# 7-Segment_SCH.net
KiCad netlist of a schematic drawn in Altium Designer
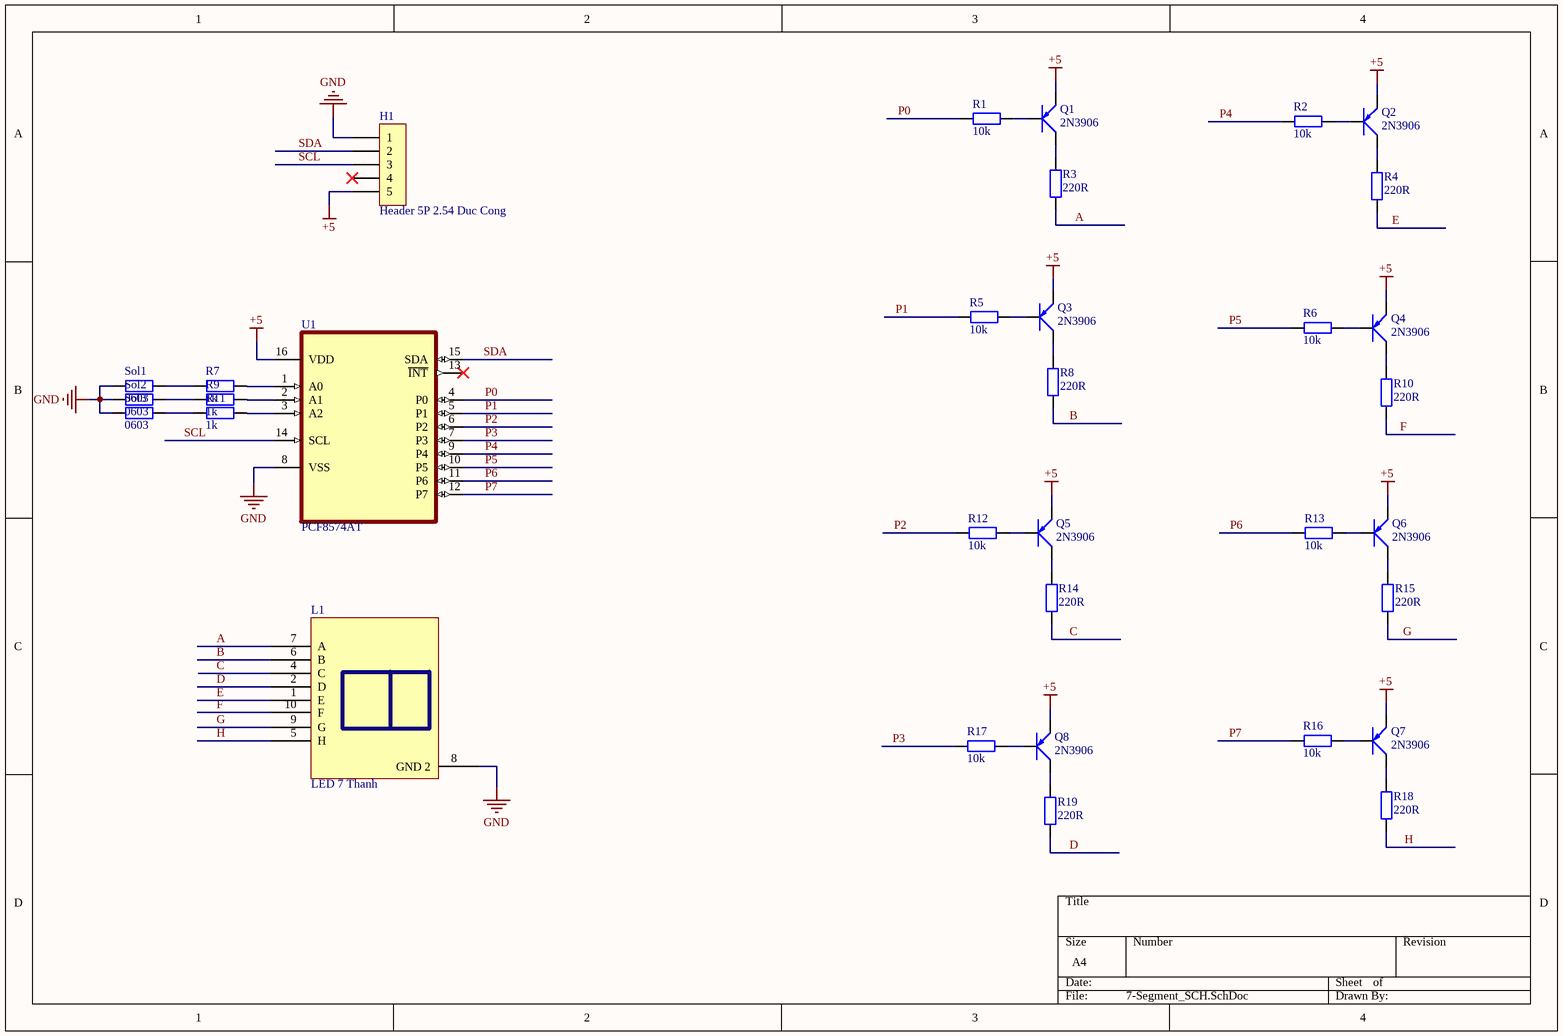
[diagram p0: 7-Segment_SCH.SchDoc]

(export (version "E")
  (design (tool "Eeschema 10.0.6"))
  (components
    (comp (ref "H1")
      (value "Header 5P 2.54 Duc Cong")
      (footprint "Header 5P DC 2.54")
      (description "Cắm")
      (libsource (lib "namnt_Lib") (part "Header 5P 2.54 Duc Cong"))
    )
    (comp (ref "L1")
      (value "LED 7 Thanh")
      (footprint "LED 7x1 0.28")
      (description "Dán")
      (libsource (lib "namnt_Lib") (part "LED 7x1 0.28 Katot"))
    )
    (comp (ref "Q1")
      (value "2N3906")
      (footprint "SOT23")
      (description "PNP 600mW, ECB")
      (libsource (lib "namnt_Lib") (part "Trans A1015 BA SMD"))
    )
    (comp (ref "Q2")
      (value "2N3906")
      (footprint "SOT23")
      (description "PNP 600mW, ECB")
      (libsource (lib "namnt_Lib") (part "Trans A1015 BA SMD"))
    )
    (comp (ref "Q3")
      (value "2N3906")
      (footprint "SOT23")
      (description "PNP 600mW, ECB")
      (libsource (lib "namnt_Lib") (part "Trans A1015 BA SMD"))
    )
    (comp (ref "Q4")
      (value "2N3906")
      (footprint "SOT23")
      (description "PNP 600mW, ECB")
      (libsource (lib "namnt_Lib") (part "Trans A1015 BA SMD"))
    )
    (comp (ref "Q5")
      (value "2N3906")
      (footprint "SOT23")
      (description "PNP 600mW, ECB")
      (libsource (lib "namnt_Lib") (part "Trans A1015 BA SMD"))
    )
    (comp (ref "Q6")
      (value "2N3906")
      (footprint "SOT23")
      (description "PNP 600mW, ECB")
      (libsource (lib "namnt_Lib") (part "Trans A1015 BA SMD"))
    )
    (comp (ref "Q7")
      (value "2N3906")
      (footprint "SOT23")
      (description "PNP 600mW, ECB")
      (libsource (lib "namnt_Lib") (part "Trans A1015 BA SMD"))
    )
    (comp (ref "Q8")
      (value "2N3906")
      (footprint "SOT23")
      (description "PNP 600mW, ECB")
      (libsource (lib "namnt_Lib") (part "Trans A1015 BA SMD"))
    )
    (comp (ref "R1")
      (value "10k")
      (footprint "tro smd 0603")
      (description "Dán")
      (libsource (lib "namnt_Lib") (part "Tro 0603 1% 10k"))
    )
    (comp (ref "R2")
      (value "10k")
      (footprint "tro smd 0603")
      (description "Dán")
      (libsource (lib "namnt_Lib") (part "Tro 0603 1% 10k"))
    )
    (comp (ref "R3")
      (value "220R")
      (footprint "tro smd 0603")
      (description "Dán")
      (libsource (lib "namnt_Lib") (part "Tro 0603 5% 220R"))
    )
    (comp (ref "R4")
      (value "220R")
      (footprint "tro smd 0603")
      (description "Dán")
      (libsource (lib "namnt_Lib") (part "Tro 0603 5% 220R"))
    )
    (comp (ref "R5")
      (value "10k")
      (footprint "tro smd 0603")
      (description "Dán")
      (libsource (lib "namnt_Lib") (part "Tro 0603 1% 10k"))
    )
    (comp (ref "R6")
      (value "10k")
      (footprint "tro smd 0603")
      (description "Dán")
      (libsource (lib "namnt_Lib") (part "Tro 0603 1% 10k"))
    )
    (comp (ref "R7")
      (value "1k")
      (footprint "tro smd 0603")
      (description "Dán")
      (libsource (lib "namnt_Lib") (part "Tro 0603 1% 1k"))
    )
    (comp (ref "R8")
      (value "220R")
      (footprint "tro smd 0603")
      (description "Dán")
      (libsource (lib "namnt_Lib") (part "Tro 0603 5% 220R"))
    )
    (comp (ref "R9")
      (value "1k")
      (footprint "tro smd 0603")
      (description "Dán")
      (libsource (lib "namnt_Lib") (part "Tro 0603 1% 1k"))
    )
    (comp (ref "R10")
      (value "220R")
      (footprint "tro smd 0603")
      (description "Dán")
      (libsource (lib "namnt_Lib") (part "Tro 0603 5% 220R"))
    )
    (comp (ref "R11")
      (value "1k")
      (footprint "tro smd 0603")
      (description "Dán")
      (libsource (lib "namnt_Lib") (part "Tro 0603 1% 1k"))
    )
    (comp (ref "R12")
      (value "10k")
      (footprint "tro smd 0603")
      (description "Dán")
      (libsource (lib "namnt_Lib") (part "Tro 0603 1% 10k"))
    )
    (comp (ref "R13")
      (value "10k")
      (footprint "tro smd 0603")
      (description "Dán")
      (libsource (lib "namnt_Lib") (part "Tro 0603 1% 10k"))
    )
    (comp (ref "R14")
      (value "220R")
      (footprint "tro smd 0603")
      (description "Dán")
      (libsource (lib "namnt_Lib") (part "Tro 0603 5% 220R"))
    )
    (comp (ref "R15")
      (value "220R")
      (footprint "tro smd 0603")
      (description "Dán")
      (libsource (lib "namnt_Lib") (part "Tro 0603 5% 220R"))
    )
    (comp (ref "R16")
      (value "10k")
      (footprint "tro smd 0603")
      (description "Dán")
      (libsource (lib "namnt_Lib") (part "Tro 0603 1% 10k"))
    )
    (comp (ref "R17")
      (value "10k")
      (footprint "tro smd 0603")
      (description "Dán")
      (libsource (lib "namnt_Lib") (part "Tro 0603 1% 10k"))
    )
    (comp (ref "R18")
      (value "220R")
      (footprint "tro smd 0603")
      (description "Dán")
      (libsource (lib "namnt_Lib") (part "Tro 0603 5% 220R"))
    )
    (comp (ref "R19")
      (value "220R")
      (footprint "tro smd 0603")
      (description "Dán")
      (libsource (lib "namnt_Lib") (part "Tro 0603 5% 220R"))
    )
    (comp (ref "Sol1")
      (value "0603")
      (footprint "Solder 0603")
      (description "Dán")
      (libsource (lib "namnt_Lib") (part "Solder 0603"))
    )
    (comp (ref "Sol2")
      (value "0603")
      (footprint "Solder 0603")
      (description "Dán")
      (libsource (lib "namnt_Lib") (part "Solder 0603"))
    )
    (comp (ref "Sol3")
      (value "0603")
      (footprint "Solder 0603")
      (description "Dán")
      (libsource (lib "namnt_Lib") (part "Solder 0603"))
    )
    (comp (ref "U1")
      (value "PCF8574AT")
      (footprint "SOIC127P1032X265-16N")
      (description "IÂ²C Bus IC Operating temperature: -40...+85 Â°C Power supply: 2.5...6 V Package: SO-16W")
      (fields (field (name "MF") "NXP USA"))
      (libsource (lib "namnt_Lib") (part "PCF8574AT"))
    )
  )
  (nets
    (net (code "1") (name "+5") (class "Default")
      (node (ref "H1") (pin "5") (pinfunction "5_5") (pintype "passive"))
      (node (ref "Q1") (pin "2") (pinfunction "E_2") (pintype "passive"))
      (node (ref "Q2") (pin "2") (pinfunction "E_2") (pintype "passive"))
      (node (ref "Q3") (pin "2") (pinfunction "E_2") (pintype "passive"))
      (node (ref "Q4") (pin "2") (pinfunction "E_2") (pintype "passive"))
      (node (ref "Q5") (pin "2") (pinfunction "E_2") (pintype "passive"))
      (node (ref "Q6") (pin "2") (pinfunction "E_2") (pintype "passive"))
      (node (ref "Q7") (pin "2") (pinfunction "E_2") (pintype "passive"))
      (node (ref "Q8") (pin "2") (pinfunction "E_2") (pintype "passive"))
      (node (ref "U1") (pin "16") (pinfunction "VDD_16") (pintype "power_in"))
    )
    (net (code "2") (name "/A") (class "Default")
      (node (ref "L1") (pin "7") (pinfunction "A_7") (pintype "passive"))
      (node (ref "R3") (pin "1") (pinfunction "1_1") (pintype "passive"))
    )
    (net (code "3") (name "/B") (class "Default")
      (node (ref "L1") (pin "6") (pinfunction "B_6") (pintype "passive"))
      (node (ref "R8") (pin "1") (pinfunction "1_1") (pintype "passive"))
    )
    (net (code "4") (name "/C") (class "Default")
      (node (ref "L1") (pin "4") (pinfunction "C_4") (pintype "passive"))
      (node (ref "R14") (pin "1") (pinfunction "1_1") (pintype "passive"))
    )
    (net (code "5") (name "/D") (class "Default")
      (node (ref "L1") (pin "2") (pinfunction "D_2") (pintype "passive"))
      (node (ref "R19") (pin "1") (pinfunction "1_1") (pintype "passive"))
    )
    (net (code "6") (name "/E") (class "Default")
      (node (ref "L1") (pin "1") (pinfunction "E_1") (pintype "passive"))
      (node (ref "R4") (pin "1") (pinfunction "1_1") (pintype "passive"))
    )
    (net (code "7") (name "/F") (class "Default")
      (node (ref "L1") (pin "10") (pinfunction "F_10") (pintype "passive"))
      (node (ref "R10") (pin "1") (pinfunction "1_1") (pintype "passive"))
    )
    (net (code "8") (name "/G") (class "Default")
      (node (ref "L1") (pin "9") (pinfunction "G_9") (pintype "passive"))
      (node (ref "R15") (pin "1") (pinfunction "1_1") (pintype "passive"))
    )
    (net (code "9") (name "/H") (class "Default")
      (node (ref "L1") (pin "5") (pinfunction "H_5") (pintype "passive"))
      (node (ref "R18") (pin "1") (pinfunction "1_1") (pintype "passive"))
    )
    (net (code "10") (name "/P0") (class "Default")
      (node (ref "R1") (pin "1") (pinfunction "1_1") (pintype "passive"))
      (node (ref "U1") (pin "4") (pinfunction "P0_4") (pintype "bidirectional"))
    )
    (net (code "11") (name "/P1") (class "Default")
      (node (ref "R5") (pin "1") (pinfunction "1_1") (pintype "passive"))
      (node (ref "U1") (pin "5") (pinfunction "P1_5") (pintype "bidirectional"))
    )
    (net (code "12") (name "/P2") (class "Default")
      (node (ref "R12") (pin "1") (pinfunction "1_1") (pintype "passive"))
      (node (ref "U1") (pin "6") (pinfunction "P2_6") (pintype "bidirectional"))
    )
    (net (code "13") (name "/P3") (class "Default")
      (node (ref "R17") (pin "1") (pinfunction "1_1") (pintype "passive"))
      (node (ref "U1") (pin "7") (pinfunction "P3_7") (pintype "bidirectional"))
    )
    (net (code "14") (name "/P4") (class "Default")
      (node (ref "R2") (pin "1") (pinfunction "1_1") (pintype "passive"))
      (node (ref "U1") (pin "9") (pinfunction "P4_9") (pintype "bidirectional"))
    )
    (net (code "15") (name "/P5") (class "Default")
      (node (ref "R6") (pin "1") (pinfunction "1_1") (pintype "passive"))
      (node (ref "U1") (pin "10") (pinfunction "P5_10") (pintype "bidirectional"))
    )
    (net (code "16") (name "/P6") (class "Default")
      (node (ref "R13") (pin "1") (pinfunction "1_1") (pintype "passive"))
      (node (ref "U1") (pin "11") (pinfunction "P6_11") (pintype "bidirectional"))
    )
    (net (code "17") (name "/P7") (class "Default")
      (node (ref "R16") (pin "1") (pinfunction "1_1") (pintype "passive"))
      (node (ref "U1") (pin "12") (pinfunction "P7_12") (pintype "bidirectional"))
    )
    (net (code "18") (name "/SCL") (class "Default")
      (node (ref "H1") (pin "3") (pinfunction "3_3") (pintype "passive"))
      (node (ref "U1") (pin "14") (pinfunction "SCL_14") (pintype "input"))
    )
    (net (code "19") (name "/SDA") (class "Default")
      (node (ref "H1") (pin "2") (pinfunction "2_2") (pintype "passive"))
      (node (ref "U1") (pin "15") (pinfunction "SDA_15") (pintype "bidirectional"))
    )
    (net (code "20") (name "GND") (class "Default")
      (node (ref "H1") (pin "1") (pinfunction "1_1") (pintype "passive"))
      (node (ref "L1") (pin "8") (pinfunction "GND_2_8") (pintype "passive"))
      (node (ref "Sol1") (pin "1") (pinfunction "1_1") (pintype "passive"))
      (node (ref "Sol2") (pin "1") (pinfunction "1_1") (pintype "passive"))
      (node (ref "Sol3") (pin "1") (pinfunction "1_1") (pintype "passive"))
      (node (ref "U1") (pin "8") (pinfunction "VSS_8") (pintype "passive"))
    )
    (net (code "21") (name "Net-(Q1-B)") (class "Default")
      (node (ref "Q1") (pin "1") (pinfunction "B_1") (pintype "passive"))
      (node (ref "R1") (pin "2") (pinfunction "2_2") (pintype "passive"))
    )
    (net (code "22") (name "Net-(Q1-C)") (class "Default")
      (node (ref "Q1") (pin "3") (pinfunction "C_3") (pintype "passive"))
      (node (ref "R3") (pin "2") (pinfunction "2_2") (pintype "passive"))
    )
    (net (code "23") (name "Net-(Q2-B)") (class "Default")
      (node (ref "Q2") (pin "1") (pinfunction "B_1") (pintype "passive"))
      (node (ref "R2") (pin "2") (pinfunction "2_2") (pintype "passive"))
    )
    (net (code "24") (name "Net-(Q2-C)") (class "Default")
      (node (ref "Q2") (pin "3") (pinfunction "C_3") (pintype "passive"))
      (node (ref "R4") (pin "2") (pinfunction "2_2") (pintype "passive"))
    )
    (net (code "25") (name "Net-(Q3-B)") (class "Default")
      (node (ref "Q3") (pin "1") (pinfunction "B_1") (pintype "passive"))
      (node (ref "R5") (pin "2") (pinfunction "2_2") (pintype "passive"))
    )
    (net (code "26") (name "Net-(Q3-C)") (class "Default")
      (node (ref "Q3") (pin "3") (pinfunction "C_3") (pintype "passive"))
      (node (ref "R8") (pin "2") (pinfunction "2_2") (pintype "passive"))
    )
    (net (code "27") (name "Net-(Q4-B)") (class "Default")
      (node (ref "Q4") (pin "1") (pinfunction "B_1") (pintype "passive"))
      (node (ref "R6") (pin "2") (pinfunction "2_2") (pintype "passive"))
    )
    (net (code "28") (name "Net-(Q4-C)") (class "Default")
      (node (ref "Q4") (pin "3") (pinfunction "C_3") (pintype "passive"))
      (node (ref "R10") (pin "2") (pinfunction "2_2") (pintype "passive"))
    )
    (net (code "29") (name "Net-(Q5-B)") (class "Default")
      (node (ref "Q5") (pin "1") (pinfunction "B_1") (pintype "passive"))
      (node (ref "R12") (pin "2") (pinfunction "2_2") (pintype "passive"))
    )
    (net (code "30") (name "Net-(Q5-C)") (class "Default")
      (node (ref "Q5") (pin "3") (pinfunction "C_3") (pintype "passive"))
      (node (ref "R14") (pin "2") (pinfunction "2_2") (pintype "passive"))
    )
    (net (code "31") (name "Net-(Q6-B)") (class "Default")
      (node (ref "Q6") (pin "1") (pinfunction "B_1") (pintype "passive"))
      (node (ref "R13") (pin "2") (pinfunction "2_2") (pintype "passive"))
    )
    (net (code "32") (name "Net-(Q6-C)") (class "Default")
      (node (ref "Q6") (pin "3") (pinfunction "C_3") (pintype "passive"))
      (node (ref "R15") (pin "2") (pinfunction "2_2") (pintype "passive"))
    )
    (net (code "33") (name "Net-(Q7-B)") (class "Default")
      (node (ref "Q7") (pin "1") (pinfunction "B_1") (pintype "passive"))
      (node (ref "R16") (pin "2") (pinfunction "2_2") (pintype "passive"))
    )
    (net (code "34") (name "Net-(Q7-C)") (class "Default")
      (node (ref "Q7") (pin "3") (pinfunction "C_3") (pintype "passive"))
      (node (ref "R18") (pin "2") (pinfunction "2_2") (pintype "passive"))
    )
    (net (code "35") (name "Net-(Q8-B)") (class "Default")
      (node (ref "Q8") (pin "1") (pinfunction "B_1") (pintype "passive"))
      (node (ref "R17") (pin "2") (pinfunction "2_2") (pintype "passive"))
    )
    (net (code "36") (name "Net-(Q8-C)") (class "Default")
      (node (ref "Q8") (pin "3") (pinfunction "C_3") (pintype "passive"))
      (node (ref "R19") (pin "2") (pinfunction "2_2") (pintype "passive"))
    )
    (net (code "37") (name "Net-(R7-Pad1)") (class "Default")
      (node (ref "R7") (pin "1") (pinfunction "1_1") (pintype "passive"))
      (node (ref "Sol1") (pin "2") (pinfunction "2_2") (pintype "passive"))
    )
    (net (code "38") (name "Net-(R9-Pad1)") (class "Default")
      (node (ref "R9") (pin "1") (pinfunction "1_1") (pintype "passive"))
      (node (ref "Sol2") (pin "2") (pinfunction "2_2") (pintype "passive"))
    )
    (net (code "39") (name "Net-(R11-Pad1)") (class "Default")
      (node (ref "R11") (pin "1") (pinfunction "1_1") (pintype "passive"))
      (node (ref "Sol3") (pin "2") (pinfunction "2_2") (pintype "passive"))
    )
    (net (code "40") (name "Net-(U1-A0)") (class "Default")
      (node (ref "R7") (pin "2") (pinfunction "2_2") (pintype "passive"))
      (node (ref "U1") (pin "1") (pinfunction "A0_1") (pintype "input"))
    )
    (net (code "41") (name "Net-(U1-A1)") (class "Default")
      (node (ref "R9") (pin "2") (pinfunction "2_2") (pintype "passive"))
      (node (ref "U1") (pin "2") (pinfunction "A1_2") (pintype "input"))
    )
    (net (code "42") (name "Net-(U1-A2)") (class "Default")
      (node (ref "R11") (pin "2") (pinfunction "2_2") (pintype "passive"))
      (node (ref "U1") (pin "3") (pinfunction "A2_3") (pintype "input"))
    )
    (net (code "43") (name "unconnected-(H1-Pad4)") (class "Default")
      (node (ref "H1") (pin "4") (pinfunction "4_4") (pintype "passive+no_connect"))
    )
    (net (code "44") (name "unconnected-(U1-~{INT}-Pad13)") (class "Default")
      (node (ref "U1") (pin "13") (pinfunction "~{INT}_13") (pintype "output+no_connect"))
    )
  )
)
